# USIPBox.net
KiCad netlist of a schematic drawn in EAGLE
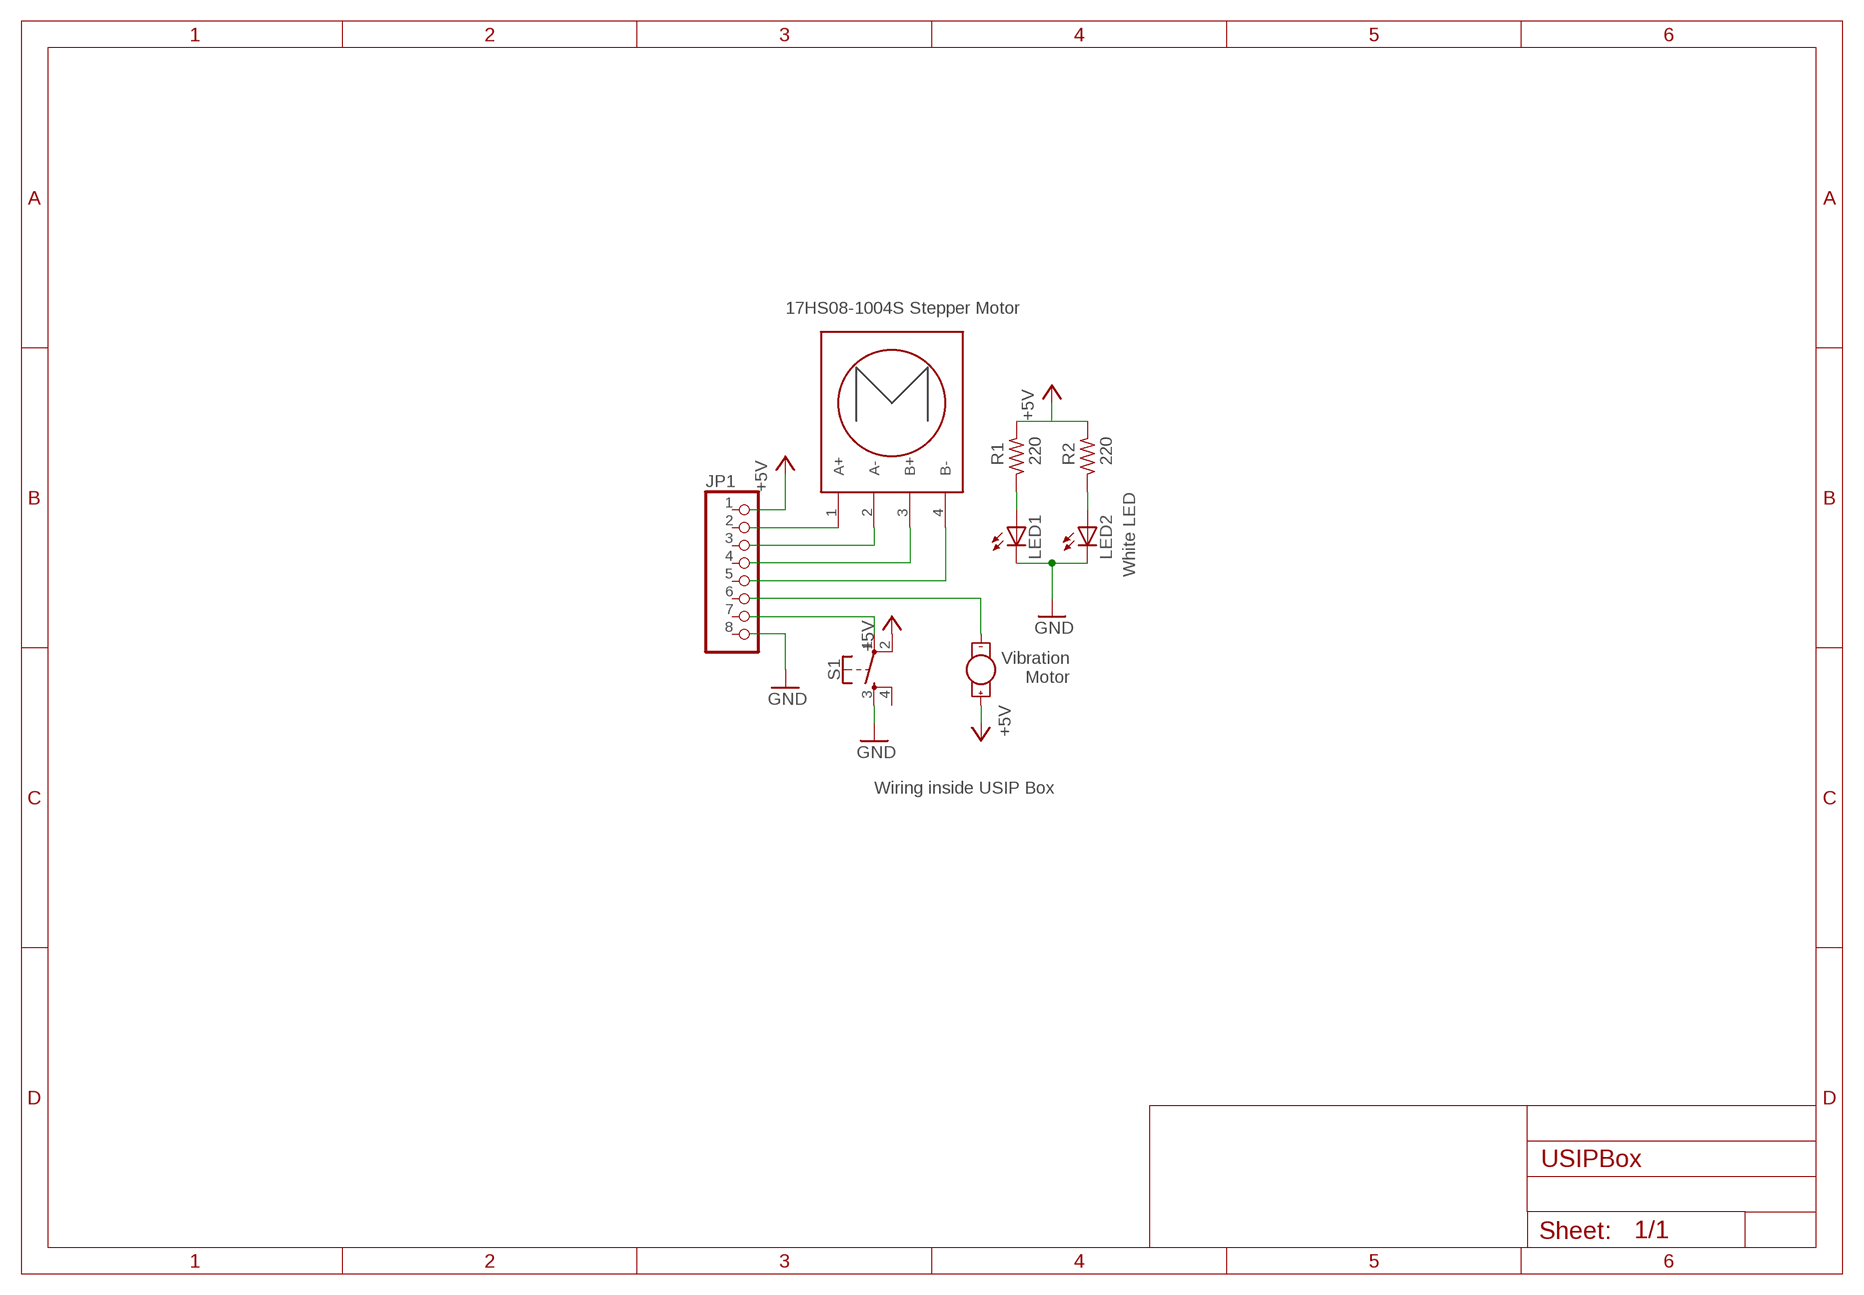
[diagram p0: schematic, sheet 1]

(export (version "E")
  (design (tool "Eeschema 10.0.6"))
  (components
    (comp (ref "JP1")
      (value "PINHD-1X8")
      (footprint "eagle-import:1X08")
      (libsource (lib "eagle-import") (part "PINHD-1X8"))
    )
    (comp (ref "LED1")
      (value "LEDB155")
      (footprint "eagle-import:Q62902-B155")
      (libsource (lib "eagle-import") (part "LEDB155"))
    )
    (comp (ref "LED2")
      (value "LEDB155")
      (footprint "eagle-import:Q62902-B155")
      (libsource (lib "eagle-import") (part "LEDB155"))
    )
    (comp (ref "M1")
      (value "MOTOR10MM")
      (footprint "eagle-import:VIBE-MOTOR-10MM")
      (libsource (lib "eagle-import") (part "MOTOR10MM"))
    )
    (comp (ref "R1")
      (value "220")
      (footprint "eagle-import:0204_5")
      (libsource (lib "eagle-import") (part "R-US_0204/5"))
    )
    (comp (ref "R2")
      (value "220")
      (footprint "eagle-import:0204_5")
      (libsource (lib "eagle-import") (part "R-US_0204/5"))
    )
    (comp (ref "S1")
      (value "MOMENTARY-SWITCH-SPST-2-SMD-5.2MM")
      (footprint "eagle-import:TACTILE_SWITCH_SMD_5.2MM")
      (libsource (lib "eagle-import") (part "MOMENTARY-SWITCH-SPST-2-SMD-5.2MM"))
    )
    (comp (ref "U$3")
      (value "STEPPER")
      (footprint "eagle-import:TC48")
      (libsource (lib "eagle-import") (part "STEPPER"))
    )
  )
  (nets
    (net (code "1") (name "+5V") (class "Default")
      (node (ref "M1") (pin "+") (pinfunction "+_+") (pintype "bidirectional"))
      (node (ref "R1") (pin "2") (pinfunction "2_2") (pintype "passive"))
      (node (ref "R2") (pin "2") (pinfunction "2_2") (pintype "passive"))
      (node (ref "S1") (pin "2") (pinfunction "2_2") (pintype "passive"))
    )
    (net (code "2") (name "GND") (class "Default")
      (node (ref "LED1") (pin "K") (pinfunction "C_K") (pintype "passive"))
      (node (ref "LED2") (pin "K") (pinfunction "C_K") (pintype "passive"))
      (node (ref "S1") (pin "3") (pinfunction "3_3") (pintype "passive"))
    )
    (net (code "3") (name "Net-(LED1-PadA)") (class "Default")
      (node (ref "LED1") (pin "A") (pinfunction "A_A") (pintype "passive"))
      (node (ref "R1") (pin "1") (pinfunction "1_1") (pintype "passive"))
    )
    (net (code "4") (name "Net-(LED2-PadA)") (class "Default")
      (node (ref "LED2") (pin "A") (pinfunction "A_A") (pintype "passive"))
      (node (ref "R2") (pin "1") (pinfunction "1_1") (pintype "passive"))
    )
    (net (code "5") (name "unconnected-(JP1-Pad1)") (class "Default")
      (node (ref "JP1") (pin "1") (pinfunction "1_1") (pintype "passive"))
    )
    (net (code "6") (name "unconnected-(JP1-Pad2)") (class "Default")
      (node (ref "JP1") (pin "2") (pinfunction "2_2") (pintype "passive"))
    )
    (net (code "7") (name "unconnected-(JP1-Pad3)") (class "Default")
      (node (ref "JP1") (pin "3") (pinfunction "3_3") (pintype "passive"))
    )
    (net (code "8") (name "unconnected-(JP1-Pad4)") (class "Default")
      (node (ref "JP1") (pin "4") (pinfunction "4_4") (pintype "passive"))
    )
    (net (code "9") (name "unconnected-(JP1-Pad5)") (class "Default")
      (node (ref "JP1") (pin "5") (pinfunction "5_5") (pintype "passive"))
    )
    (net (code "10") (name "unconnected-(JP1-Pad6)") (class "Default")
      (node (ref "JP1") (pin "6") (pinfunction "6_6") (pintype "passive"))
    )
    (net (code "11") (name "unconnected-(JP1-Pad7)") (class "Default")
      (node (ref "JP1") (pin "7") (pinfunction "7_7") (pintype "passive"))
    )
    (net (code "12") (name "unconnected-(JP1-Pad8)") (class "Default")
      (node (ref "JP1") (pin "8") (pinfunction "8_8") (pintype "passive"))
    )
    (net (code "13") (name "unconnected-(M1-Pad-)") (class "Default")
      (node (ref "M1") (pin "-") (pinfunction "-_-") (pintype "bidirectional"))
    )
    (net (code "14") (name "unconnected-(S1-Pad1)") (class "Default")
      (node (ref "S1") (pin "1") (pinfunction "1_1") (pintype "passive"))
    )
    (net (code "15") (name "unconnected-(S1-Pad4)") (class "Default")
      (node (ref "S1") (pin "4") (pinfunction "4_4") (pintype "passive"))
    )
    (net (code "16") (name "unconnected-(U$3-A+-Pad1)") (class "Default")
      (node (ref "U$3") (pin "1") (pinfunction "A+_1") (pintype "bidirectional"))
    )
    (net (code "17") (name "unconnected-(U$3-A--Pad2)") (class "Default")
      (node (ref "U$3") (pin "2") (pinfunction "A-_2") (pintype "bidirectional"))
    )
    (net (code "18") (name "unconnected-(U$3-B+-Pad3)") (class "Default")
      (node (ref "U$3") (pin "3") (pinfunction "B+_3") (pintype "bidirectional"))
    )
    (net (code "19") (name "unconnected-(U$3-B--Pad4)") (class "Default")
      (node (ref "U$3") (pin "4") (pinfunction "B-_4") (pintype "bidirectional"))
    )
  )
)
